# TTGO_shield_revC.net
KiCad netlist of a schematic drawn in EAGLE
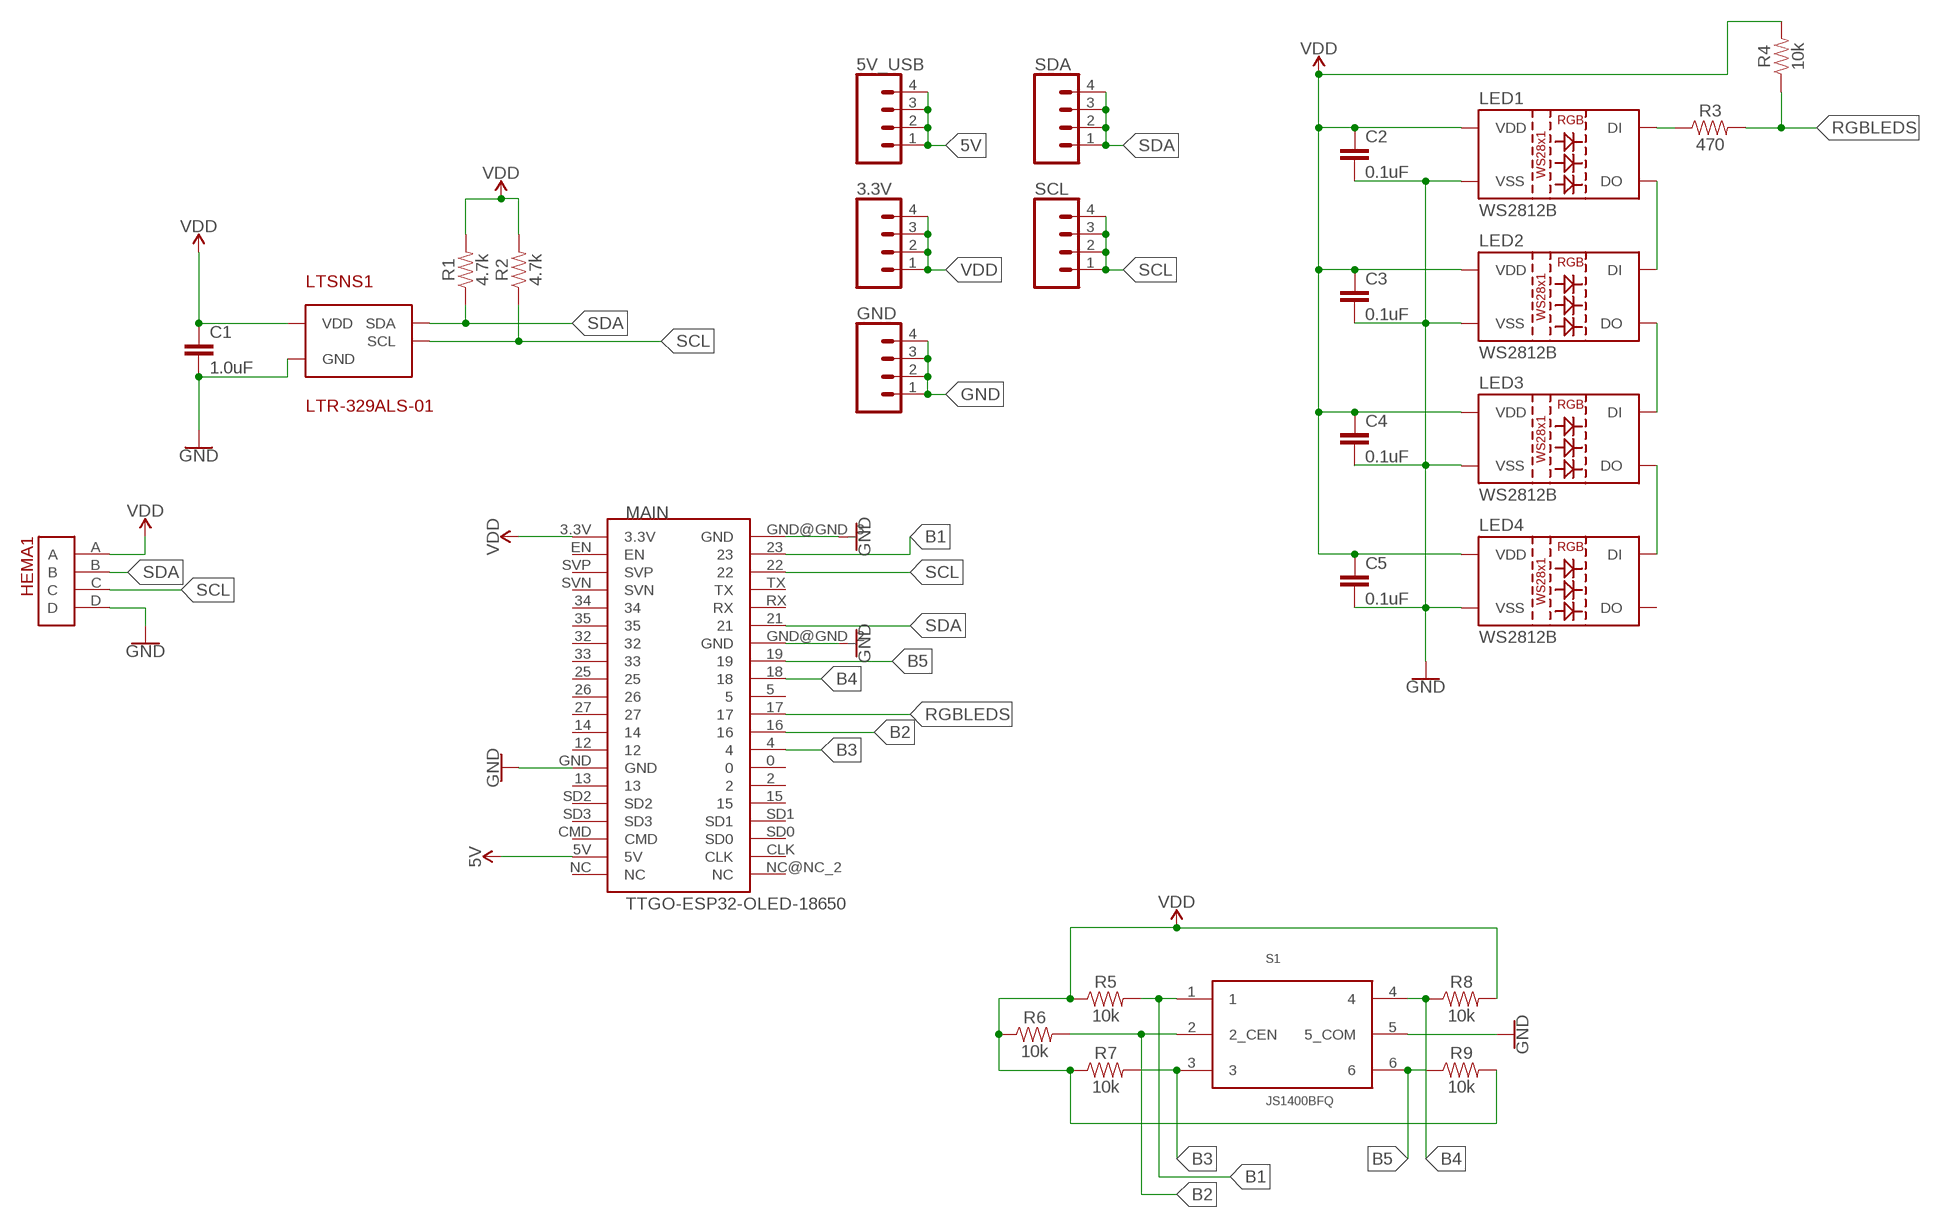
[diagram p0: schematic, sheet 1]

(export (version "E")
  (design (tool "Eeschema 10.0.6"))
  (components
    (comp (ref "3.3V")
      (value "CONN_041X04_NO_SILK")
      (footprint "eagle-import:1X04_NO_SILK")
      (libsource (lib "eagle-import") (part "CONN_041X04_NO_SILK"))
    )
    (comp (ref "5V_USB")
      (value "CONN_041X04_NO_SILK")
      (footprint "eagle-import:1X04_NO_SILK")
      (libsource (lib "eagle-import") (part "CONN_041X04_NO_SILK"))
    )
    (comp (ref "C1")
      (value "1.0uF")
      (footprint "eagle-import:0805")
      (libsource (lib "eagle-import") (part "1.0UF-0805-25V-10%"))
    )
    (comp (ref "C2")
      (value "0.1uF")
      (footprint "eagle-import:0603")
      (libsource (lib "eagle-import") (part "0.1UF-0603-25V-5%"))
    )
    (comp (ref "C3")
      (value "0.1uF")
      (footprint "eagle-import:0603")
      (libsource (lib "eagle-import") (part "0.1UF-0603-25V-5%"))
    )
    (comp (ref "C4")
      (value "0.1uF")
      (footprint "eagle-import:0603")
      (libsource (lib "eagle-import") (part "0.1UF-0603-25V-5%"))
    )
    (comp (ref "C5")
      (value "0.1uF")
      (footprint "eagle-import:0603")
      (libsource (lib "eagle-import") (part "0.1UF-0603-25V-5%"))
    )
    (comp (ref "GND")
      (value "CONN_041X04_NO_SILK")
      (footprint "eagle-import:1X04_NO_SILK")
      (libsource (lib "eagle-import") (part "CONN_041X04_NO_SILK"))
    )
    (comp (ref "HEMA1")
      (value "10120045-400LF")
      (footprint "eagle-import:10120045-400LF")
      (libsource (lib "eagle-import") (part "10120045-400LF"))
    )
    (comp (ref "LED1")
      (value "WS2812B")
      (footprint "eagle-import:WS2812B")
      (libsource (lib "eagle-import") (part "WS2812B"))
    )
    (comp (ref "LED2")
      (value "WS2812B")
      (footprint "eagle-import:WS2812B")
      (libsource (lib "eagle-import") (part "WS2812B"))
    )
    (comp (ref "LED3")
      (value "WS2812B")
      (footprint "eagle-import:WS2812B")
      (libsource (lib "eagle-import") (part "WS2812B"))
    )
    (comp (ref "LED4")
      (value "WS2812B")
      (footprint "eagle-import:WS2812B")
      (libsource (lib "eagle-import") (part "WS2812B"))
    )
    (comp (ref "LTSNS1")
      (value "LTR-329ALS-01")
      (footprint "eagle-import:CHIPLED-4")
      (libsource (lib "eagle-import") (part "LTR-329ALS-01"))
    )
    (comp (ref "MAIN")
      (value "TTGO-ESP32-OLED-18650")
      (footprint "eagle-import:TTGO-ESP32-OLED-18650")
      (libsource (lib "eagle-import") (part "TTGO-ESP32-OLED-18650"))
    )
    (comp (ref "R1")
      (value "4.7k")
      (footprint "eagle-import:0603")
      (libsource (lib "eagle-import") (part "4.7KOHM-0603-1/10W-1%"))
    )
    (comp (ref "R2")
      (value "4.7k")
      (footprint "eagle-import:0603")
      (libsource (lib "eagle-import") (part "4.7KOHM-0603-1/10W-1%"))
    )
    (comp (ref "R3")
      (value "470")
      (footprint "eagle-import:0603")
      (libsource (lib "eagle-import") (part "470OHM-0603-1/10W-1%"))
    )
    (comp (ref "R4")
      (value "10k")
      (footprint "eagle-import:0603")
      (libsource (lib "eagle-import") (part "10KOHM-0603-1/10W-1%"))
    )
    (comp (ref "R5")
      (value "10k")
      (footprint "eagle-import:0603")
      (libsource (lib "eagle-import") (part "10KOHM-0603-1/10W-1%"))
    )
    (comp (ref "R6")
      (value "10k")
      (footprint "eagle-import:0603")
      (libsource (lib "eagle-import") (part "10KOHM-0603-1/10W-1%"))
    )
    (comp (ref "R7")
      (value "10k")
      (footprint "eagle-import:0603")
      (libsource (lib "eagle-import") (part "10KOHM-0603-1/10W-1%"))
    )
    (comp (ref "R8")
      (value "10k")
      (footprint "eagle-import:0603")
      (libsource (lib "eagle-import") (part "10KOHM-0603-1/10W-1%"))
    )
    (comp (ref "R9")
      (value "10k")
      (footprint "eagle-import:0603")
      (libsource (lib "eagle-import") (part "10KOHM-0603-1/10W-1%"))
    )
    (comp (ref "S1")
      (value "JS1400BFQ")
      (footprint "eagle-import:JS1400BFQ")
      (libsource (lib "eagle-import") (part "JS1400BFQ"))
    )
    (comp (ref "SCL")
      (value "CONN_041X04_NO_SILK")
      (footprint "eagle-import:1X04_NO_SILK")
      (libsource (lib "eagle-import") (part "CONN_041X04_NO_SILK"))
    )
    (comp (ref "SDA")
      (value "CONN_041X04_NO_SILK")
      (footprint "eagle-import:1X04_NO_SILK")
      (libsource (lib "eagle-import") (part "CONN_041X04_NO_SILK"))
    )
  )
  (nets
    (net (code "1") (name "5V") (class "Default")
      (node (ref "5V_USB") (pin "1") (pinfunction "1_1") (pintype "passive"))
      (node (ref "5V_USB") (pin "2") (pinfunction "2_2") (pintype "passive"))
      (node (ref "5V_USB") (pin "3") (pinfunction "3_3") (pintype "passive"))
      (node (ref "5V_USB") (pin "4") (pinfunction "4_4") (pintype "passive"))
      (node (ref "MAIN") (pin "5V") (pinfunction "5V_5V") (pintype "bidirectional"))
    )
    (net (code "2") (name "B1") (class "Default")
      (node (ref "MAIN") (pin "23") (pinfunction "23_23") (pintype "bidirectional"))
      (node (ref "R5") (pin "2") (pinfunction "2_2") (pintype "passive"))
      (node (ref "S1") (pin "1") (pinfunction "1_1") (pintype "bidirectional"))
    )
    (net (code "3") (name "B2") (class "Default")
      (node (ref "MAIN") (pin "16") (pinfunction "16_16") (pintype "bidirectional"))
      (node (ref "R6") (pin "2") (pinfunction "2_2") (pintype "passive"))
      (node (ref "S1") (pin "2") (pinfunction "2_CEN_2") (pintype "bidirectional"))
    )
    (net (code "4") (name "B3") (class "Default")
      (node (ref "MAIN") (pin "4") (pinfunction "4_4") (pintype "bidirectional"))
      (node (ref "R7") (pin "2") (pinfunction "2_2") (pintype "passive"))
      (node (ref "S1") (pin "3") (pinfunction "3_3") (pintype "bidirectional"))
    )
    (net (code "5") (name "B4") (class "Default")
      (node (ref "MAIN") (pin "18") (pinfunction "18_18") (pintype "bidirectional"))
      (node (ref "R8") (pin "1") (pinfunction "1_1") (pintype "passive"))
      (node (ref "S1") (pin "4") (pinfunction "4_4") (pintype "bidirectional"))
    )
    (net (code "6") (name "B5") (class "Default")
      (node (ref "MAIN") (pin "19") (pinfunction "19_19") (pintype "bidirectional"))
      (node (ref "R9") (pin "1") (pinfunction "1_1") (pintype "passive"))
      (node (ref "S1") (pin "6") (pinfunction "6_6") (pintype "bidirectional"))
    )
    (net (code "7") (name "GND") (class "Default")
      (node (ref "C1") (pin "2") (pinfunction "2_2") (pintype "passive"))
      (node (ref "C2") (pin "2") (pinfunction "2_2") (pintype "passive"))
      (node (ref "C3") (pin "2") (pinfunction "2_2") (pintype "passive"))
      (node (ref "C4") (pin "2") (pinfunction "2_2") (pintype "passive"))
      (node (ref "C5") (pin "2") (pinfunction "2_2") (pintype "passive"))
      (node (ref "GND") (pin "1") (pinfunction "1_1") (pintype "passive"))
      (node (ref "GND") (pin "2") (pinfunction "2_2") (pintype "passive"))
      (node (ref "GND") (pin "3") (pinfunction "3_3") (pintype "passive"))
      (node (ref "GND") (pin "4") (pinfunction "4_4") (pintype "passive"))
      (node (ref "HEMA1") (pin "D") (pinfunction "D_D") (pintype "bidirectional"))
      (node (ref "LED1") (pin "3") (pinfunction "VSS_3") (pintype "bidirectional"))
      (node (ref "LED2") (pin "3") (pinfunction "VSS_3") (pintype "bidirectional"))
      (node (ref "LED3") (pin "3") (pinfunction "VSS_3") (pintype "bidirectional"))
      (node (ref "LED4") (pin "3") (pinfunction "VSS_3") (pintype "bidirectional"))
      (node (ref "LTSNS1") (pin "2") (pinfunction "GND_2") (pintype "bidirectional"))
      (node (ref "MAIN") (pin "GND") (pinfunction "GND_GND") (pintype "bidirectional"))
      (node (ref "MAIN") (pin "GND@GND_2") (pinfunction "GND_GND@GND_2") (pintype "bidirectional"))
      (node (ref "MAIN") (pin "GND@GND_3") (pinfunction "GND_GND@GND_3") (pintype "bidirectional"))
      (node (ref "S1") (pin "5") (pinfunction "5_COM_5") (pintype "bidirectional"))
    )
    (net (code "8") (name "Net-(LED1-DI)") (class "Default")
      (node (ref "LED1") (pin "4") (pinfunction "DI_4") (pintype "bidirectional"))
      (node (ref "R3") (pin "1") (pinfunction "1_1") (pintype "passive"))
    )
    (net (code "9") (name "Net-(LED1-DO)") (class "Default")
      (node (ref "LED1") (pin "2") (pinfunction "DO_2") (pintype "bidirectional"))
      (node (ref "LED2") (pin "4") (pinfunction "DI_4") (pintype "bidirectional"))
    )
    (net (code "10") (name "Net-(LED2-DO)") (class "Default")
      (node (ref "LED2") (pin "2") (pinfunction "DO_2") (pintype "bidirectional"))
      (node (ref "LED3") (pin "4") (pinfunction "DI_4") (pintype "bidirectional"))
    )
    (net (code "11") (name "Net-(LED3-DO)") (class "Default")
      (node (ref "LED3") (pin "2") (pinfunction "DO_2") (pintype "bidirectional"))
      (node (ref "LED4") (pin "4") (pinfunction "DI_4") (pintype "bidirectional"))
    )
    (net (code "12") (name "RGBLEDS") (class "Default")
      (node (ref "MAIN") (pin "17") (pinfunction "17_17") (pintype "bidirectional"))
      (node (ref "R3") (pin "2") (pinfunction "2_2") (pintype "passive"))
      (node (ref "R4") (pin "1") (pinfunction "1_1") (pintype "passive"))
    )
    (net (code "13") (name "SCL") (class "Default")
      (node (ref "HEMA1") (pin "C") (pinfunction "C_C") (pintype "bidirectional"))
      (node (ref "LTSNS1") (pin "4") (pinfunction "SCL_4") (pintype "bidirectional"))
      (node (ref "MAIN") (pin "22") (pinfunction "22_22") (pintype "bidirectional"))
      (node (ref "R2") (pin "1") (pinfunction "1_1") (pintype "passive"))
      (node (ref "SCL") (pin "1") (pinfunction "1_1") (pintype "passive"))
      (node (ref "SCL") (pin "2") (pinfunction "2_2") (pintype "passive"))
      (node (ref "SCL") (pin "3") (pinfunction "3_3") (pintype "passive"))
      (node (ref "SCL") (pin "4") (pinfunction "4_4") (pintype "passive"))
    )
    (net (code "14") (name "SDA") (class "Default")
      (node (ref "HEMA1") (pin "B") (pinfunction "B_B") (pintype "bidirectional"))
      (node (ref "LTSNS1") (pin "3") (pinfunction "SDA_3") (pintype "bidirectional"))
      (node (ref "MAIN") (pin "21") (pinfunction "21_21") (pintype "bidirectional"))
      (node (ref "R1") (pin "1") (pinfunction "1_1") (pintype "passive"))
      (node (ref "SDA") (pin "1") (pinfunction "1_1") (pintype "passive"))
      (node (ref "SDA") (pin "2") (pinfunction "2_2") (pintype "passive"))
      (node (ref "SDA") (pin "3") (pinfunction "3_3") (pintype "passive"))
      (node (ref "SDA") (pin "4") (pinfunction "4_4") (pintype "passive"))
    )
    (net (code "15") (name "VDD") (class "Default")
      (node (ref "3.3V") (pin "1") (pinfunction "1_1") (pintype "passive"))
      (node (ref "3.3V") (pin "2") (pinfunction "2_2") (pintype "passive"))
      (node (ref "3.3V") (pin "3") (pinfunction "3_3") (pintype "passive"))
      (node (ref "3.3V") (pin "4") (pinfunction "4_4") (pintype "passive"))
      (node (ref "C1") (pin "1") (pinfunction "1_1") (pintype "passive"))
      (node (ref "C2") (pin "1") (pinfunction "1_1") (pintype "passive"))
      (node (ref "C3") (pin "1") (pinfunction "1_1") (pintype "passive"))
      (node (ref "C4") (pin "1") (pinfunction "1_1") (pintype "passive"))
      (node (ref "C5") (pin "1") (pinfunction "1_1") (pintype "passive"))
      (node (ref "HEMA1") (pin "A") (pinfunction "A_A") (pintype "bidirectional"))
      (node (ref "LED1") (pin "1") (pinfunction "VDD_1") (pintype "bidirectional"))
      (node (ref "LED2") (pin "1") (pinfunction "VDD_1") (pintype "bidirectional"))
      (node (ref "LED3") (pin "1") (pinfunction "VDD_1") (pintype "bidirectional"))
      (node (ref "LED4") (pin "1") (pinfunction "VDD_1") (pintype "bidirectional"))
      (node (ref "LTSNS1") (pin "1") (pinfunction "VDD_1") (pintype "bidirectional"))
      (node (ref "MAIN") (pin "3.3V") (pinfunction "3.3V_3.3V") (pintype "bidirectional"))
      (node (ref "R1") (pin "2") (pinfunction "2_2") (pintype "passive"))
      (node (ref "R2") (pin "2") (pinfunction "2_2") (pintype "passive"))
      (node (ref "R4") (pin "2") (pinfunction "2_2") (pintype "passive"))
      (node (ref "R5") (pin "1") (pinfunction "1_1") (pintype "passive"))
      (node (ref "R6") (pin "1") (pinfunction "1_1") (pintype "passive"))
      (node (ref "R7") (pin "1") (pinfunction "1_1") (pintype "passive"))
      (node (ref "R8") (pin "2") (pinfunction "2_2") (pintype "passive"))
      (node (ref "R9") (pin "2") (pinfunction "2_2") (pintype "passive"))
    )
    (net (code "16") (name "unconnected-(LED4-DO-Pad2)") (class "Default")
      (node (ref "LED4") (pin "2") (pinfunction "DO_2") (pintype "bidirectional"))
    )
    (net (code "17") (name "unconnected-(MAIN-NC-PadNC@NC_2)") (class "Default")
      (node (ref "MAIN") (pin "NC@NC_2") (pinfunction "NC_NC@NC_2") (pintype "bidirectional"))
    )
    (net (code "18") (name "unconnected-(MAIN-Pad0)") (class "Default")
      (node (ref "MAIN") (pin "0") (pinfunction "0_0") (pintype "bidirectional"))
    )
    (net (code "19") (name "unconnected-(MAIN-Pad2)") (class "Default")
      (node (ref "MAIN") (pin "2") (pinfunction "2_2") (pintype "bidirectional"))
    )
    (net (code "20") (name "unconnected-(MAIN-Pad5)") (class "Default")
      (node (ref "MAIN") (pin "5") (pinfunction "5_5") (pintype "bidirectional"))
    )
    (net (code "21") (name "unconnected-(MAIN-Pad12)") (class "Default")
      (node (ref "MAIN") (pin "12") (pinfunction "12_12") (pintype "bidirectional"))
    )
    (net (code "22") (name "unconnected-(MAIN-Pad13)") (class "Default")
      (node (ref "MAIN") (pin "13") (pinfunction "13_13") (pintype "bidirectional"))
    )
    (net (code "23") (name "unconnected-(MAIN-Pad14)") (class "Default")
      (node (ref "MAIN") (pin "14") (pinfunction "14_14") (pintype "bidirectional"))
    )
    (net (code "24") (name "unconnected-(MAIN-Pad15)") (class "Default")
      (node (ref "MAIN") (pin "15") (pinfunction "15_15") (pintype "bidirectional"))
    )
    (net (code "25") (name "unconnected-(MAIN-Pad25)") (class "Default")
      (node (ref "MAIN") (pin "25") (pinfunction "25_25") (pintype "bidirectional"))
    )
    (net (code "26") (name "unconnected-(MAIN-Pad26)") (class "Default")
      (node (ref "MAIN") (pin "26") (pinfunction "26_26") (pintype "bidirectional"))
    )
    (net (code "27") (name "unconnected-(MAIN-Pad27)") (class "Default")
      (node (ref "MAIN") (pin "27") (pinfunction "27_27") (pintype "bidirectional"))
    )
    (net (code "28") (name "unconnected-(MAIN-Pad32)") (class "Default")
      (node (ref "MAIN") (pin "32") (pinfunction "32_32") (pintype "bidirectional"))
    )
    (net (code "29") (name "unconnected-(MAIN-Pad33)") (class "Default")
      (node (ref "MAIN") (pin "33") (pinfunction "33_33") (pintype "bidirectional"))
    )
    (net (code "30") (name "unconnected-(MAIN-Pad34)") (class "Default")
      (node (ref "MAIN") (pin "34") (pinfunction "34_34") (pintype "bidirectional"))
    )
    (net (code "31") (name "unconnected-(MAIN-Pad35)") (class "Default")
      (node (ref "MAIN") (pin "35") (pinfunction "35_35") (pintype "bidirectional"))
    )
    (net (code "32") (name "unconnected-(MAIN-PadCLK)") (class "Default")
      (node (ref "MAIN") (pin "CLK") (pinfunction "CLK_CLK") (pintype "bidirectional"))
    )
    (net (code "33") (name "unconnected-(MAIN-PadCMD)") (class "Default")
      (node (ref "MAIN") (pin "CMD") (pinfunction "CMD_CMD") (pintype "bidirectional"))
    )
    (net (code "34") (name "unconnected-(MAIN-PadEN)") (class "Default")
      (node (ref "MAIN") (pin "EN") (pinfunction "EN_EN") (pintype "bidirectional"))
    )
    (net (code "35") (name "unconnected-(MAIN-PadNC)") (class "Default")
      (node (ref "MAIN") (pin "NC") (pinfunction "NC_NC") (pintype "bidirectional"))
    )
    (net (code "36") (name "unconnected-(MAIN-PadRX)") (class "Default")
      (node (ref "MAIN") (pin "RX") (pinfunction "RX_RX") (pintype "bidirectional"))
    )
    (net (code "37") (name "unconnected-(MAIN-PadSD0)") (class "Default")
      (node (ref "MAIN") (pin "SD0") (pinfunction "SD0_SD0") (pintype "bidirectional"))
    )
    (net (code "38") (name "unconnected-(MAIN-PadSD1)") (class "Default")
      (node (ref "MAIN") (pin "SD1") (pinfunction "SD1_SD1") (pintype "bidirectional"))
    )
    (net (code "39") (name "unconnected-(MAIN-PadSD2)") (class "Default")
      (node (ref "MAIN") (pin "SD2") (pinfunction "SD2_SD2") (pintype "bidirectional"))
    )
    (net (code "40") (name "unconnected-(MAIN-PadSD3)") (class "Default")
      (node (ref "MAIN") (pin "SD3") (pinfunction "SD3_SD3") (pintype "bidirectional"))
    )
    (net (code "41") (name "unconnected-(MAIN-PadSVN)") (class "Default")
      (node (ref "MAIN") (pin "SVN") (pinfunction "SVN_SVN") (pintype "bidirectional"))
    )
    (net (code "42") (name "unconnected-(MAIN-PadSVP)") (class "Default")
      (node (ref "MAIN") (pin "SVP") (pinfunction "SVP_SVP") (pintype "bidirectional"))
    )
    (net (code "43") (name "unconnected-(MAIN-PadTX)") (class "Default")
      (node (ref "MAIN") (pin "TX") (pinfunction "TX_TX") (pintype "bidirectional"))
    )
  )
)
